# DAC_adapter_V2.net
KiCad netlist of a schematic drawn in EAGLE
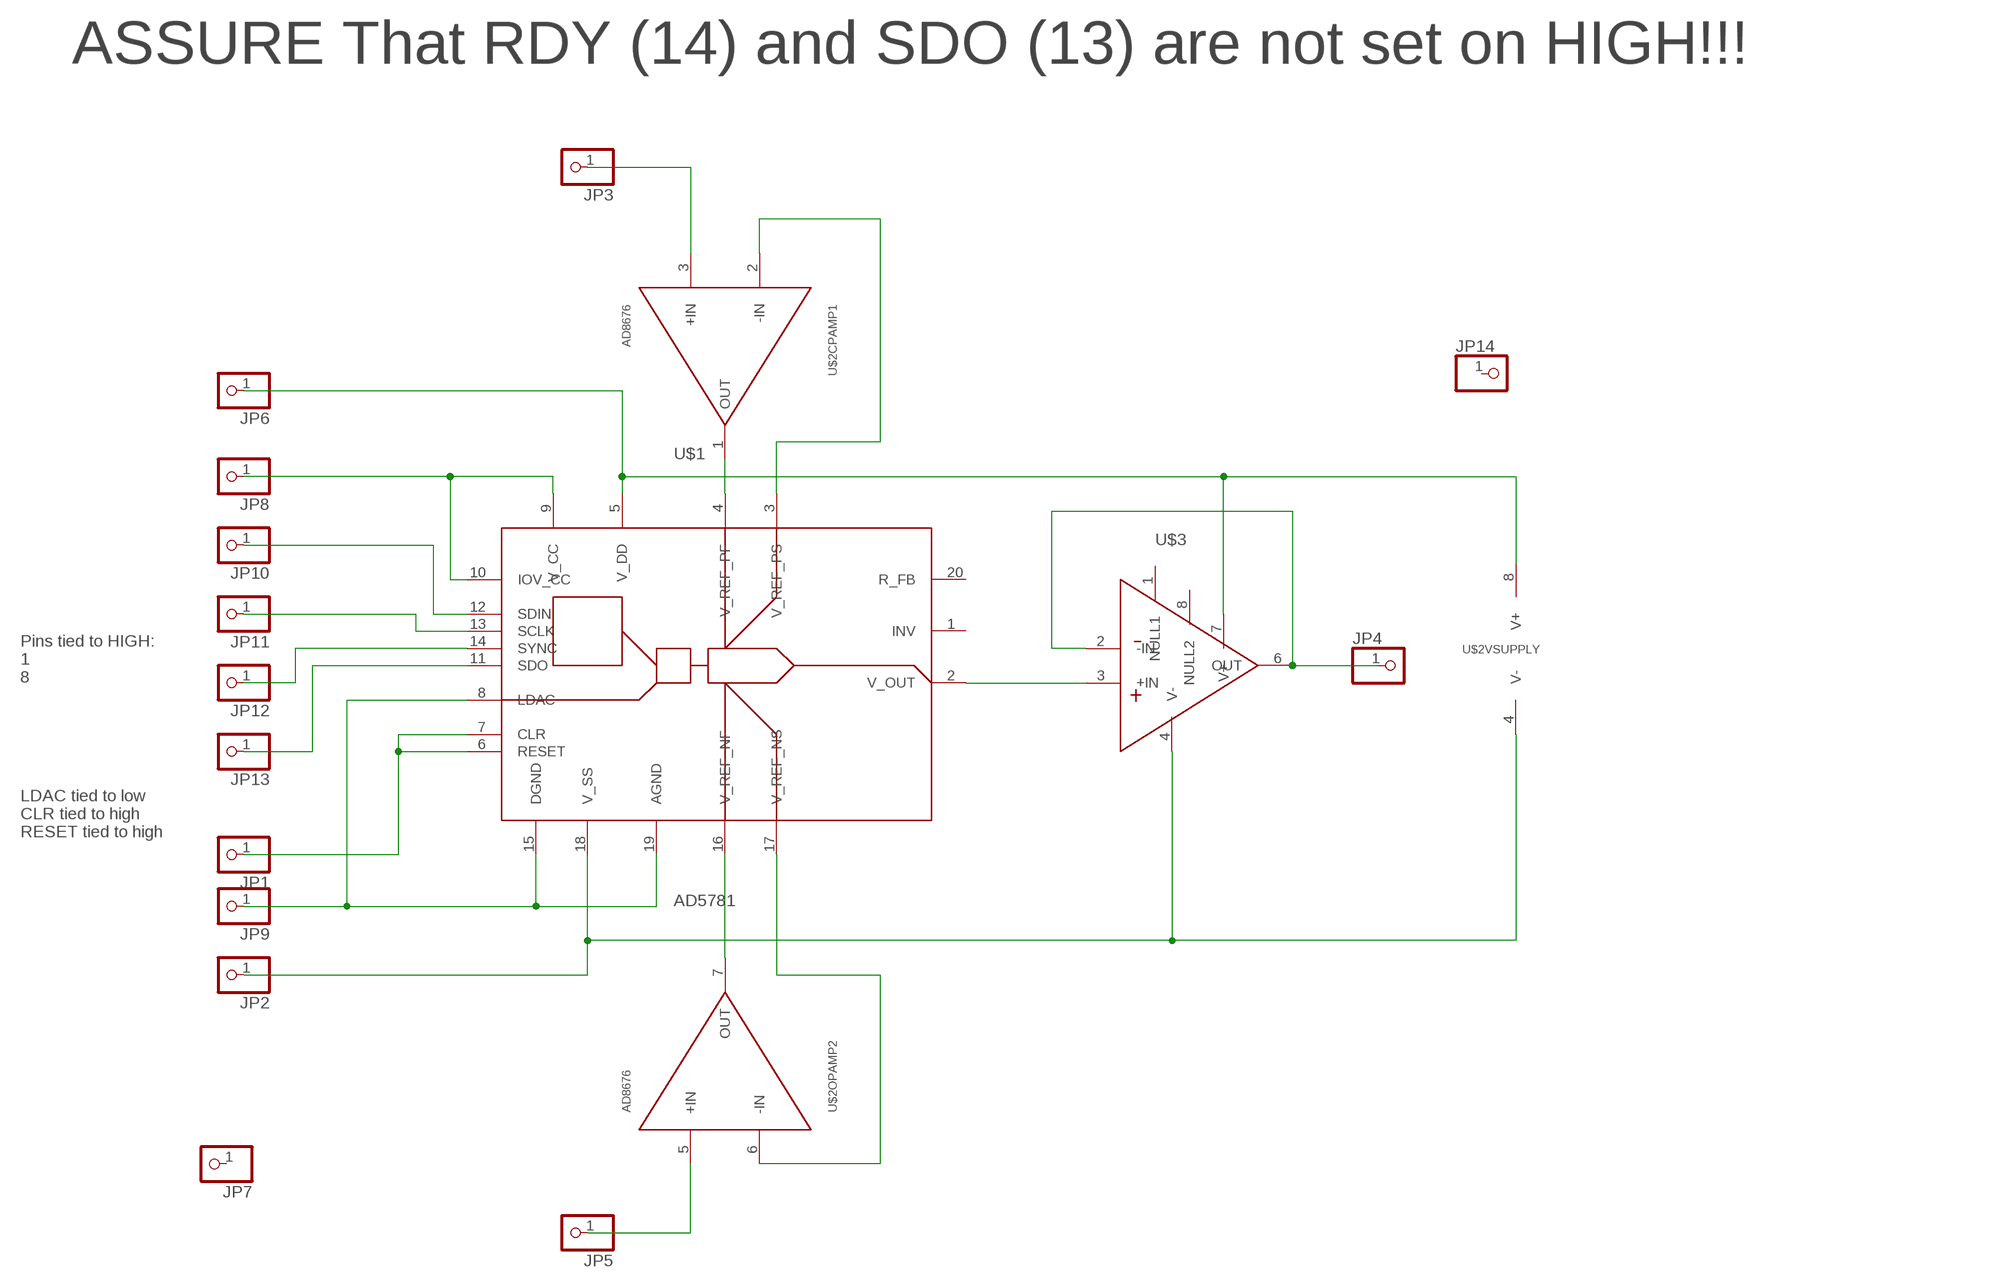
[diagram p0: schematic, sheet 1]

(export (version "E")
  (design (tool "Eeschema 10.0.6"))
  (components
    (comp (ref "JP1")
      (value "PINHD-1X1")
      (footprint "eagle-import:1X01")
      (libsource (lib "eagle-import") (part "PINHD-1X1"))
    )
    (comp (ref "JP2")
      (value "PINHD-1X1")
      (footprint "eagle-import:1X01")
      (libsource (lib "eagle-import") (part "PINHD-1X1"))
    )
    (comp (ref "JP3")
      (value "PINHD-1X1")
      (footprint "eagle-import:1X01")
      (libsource (lib "eagle-import") (part "PINHD-1X1"))
    )
    (comp (ref "JP4")
      (value "PINHD-1X1")
      (footprint "eagle-import:1X01")
      (libsource (lib "eagle-import") (part "PINHD-1X1"))
    )
    (comp (ref "JP5")
      (value "PINHD-1X1")
      (footprint "eagle-import:1X01")
      (libsource (lib "eagle-import") (part "PINHD-1X1"))
    )
    (comp (ref "JP6")
      (value "PINHD-1X1")
      (footprint "eagle-import:1X01")
      (libsource (lib "eagle-import") (part "PINHD-1X1"))
    )
    (comp (ref "JP7")
      (value "PINHD-1X1")
      (footprint "eagle-import:1X01")
      (libsource (lib "eagle-import") (part "PINHD-1X1"))
    )
    (comp (ref "JP8")
      (value "PINHD-1X1")
      (footprint "eagle-import:1X01")
      (libsource (lib "eagle-import") (part "PINHD-1X1"))
    )
    (comp (ref "JP9")
      (value "PINHD-1X1")
      (footprint "eagle-import:1X01")
      (libsource (lib "eagle-import") (part "PINHD-1X1"))
    )
    (comp (ref "JP10")
      (value "PINHD-1X1")
      (footprint "eagle-import:1X01")
      (libsource (lib "eagle-import") (part "PINHD-1X1"))
    )
    (comp (ref "JP11")
      (value "PINHD-1X1")
      (footprint "eagle-import:1X01")
      (libsource (lib "eagle-import") (part "PINHD-1X1"))
    )
    (comp (ref "JP12")
      (value "PINHD-1X1")
      (footprint "eagle-import:1X01")
      (libsource (lib "eagle-import") (part "PINHD-1X1"))
    )
    (comp (ref "JP13")
      (value "PINHD-1X1")
      (footprint "eagle-import:1X01")
      (libsource (lib "eagle-import") (part "PINHD-1X1"))
    )
    (comp (ref "JP14")
      (value "PINHD-1X1")
      (footprint "eagle-import:1X01")
      (libsource (lib "eagle-import") (part "PINHD-1X1"))
    )
    (comp (ref "U$1")
      (value "AD5781")
      (footprint "eagle-import:TSSOP20")
      (libsource (lib "eagle-import") (part "AD5781"))
    )
    (comp (ref "U$2")
      (value "AD8676")
      (footprint "eagle-import:MSOP08")
      (libsource (lib "eagle-import") (part "AD8676"))
    )
    (comp (ref "U$3")
      (value "AD8675")
      (footprint "eagle-import:MSOP08")
      (libsource (lib "eagle-import") (part "AD8675"))
    )
  )
  (nets
    (net (code "1") (name "Net-(U$1-AGND)") (class "Default")
      (node (ref "JP9") (pin "1") (pinfunction "1_1") (pintype "passive"))
      (node (ref "U$1") (pin "15") (pinfunction "DGND_15") (pintype "bidirectional"))
      (node (ref "U$1") (pin "19") (pinfunction "AGND_19") (pintype "bidirectional"))
      (node (ref "U$1") (pin "8") (pinfunction "LDAC_8") (pintype "bidirectional"))
    )
    (net (code "2") (name "Net-(U$1-CLR)") (class "Default")
      (node (ref "JP1") (pin "1") (pinfunction "1_1") (pintype "passive"))
      (node (ref "U$1") (pin "6") (pinfunction "RESET_6") (pintype "bidirectional"))
      (node (ref "U$1") (pin "7") (pinfunction "CLR_7") (pintype "bidirectional"))
    )
    (net (code "3") (name "Net-(U$1-IOV_CC)") (class "Default")
      (node (ref "JP8") (pin "1") (pinfunction "1_1") (pintype "passive"))
      (node (ref "U$1") (pin "10") (pinfunction "IOV_CC_10") (pintype "bidirectional"))
      (node (ref "U$1") (pin "9") (pinfunction "V_CC_9") (pintype "bidirectional"))
    )
    (net (code "4") (name "Net-(U$1-SCLK)") (class "Default")
      (node (ref "JP11") (pin "1") (pinfunction "1_1") (pintype "passive"))
      (node (ref "U$1") (pin "13") (pinfunction "SCLK_13") (pintype "bidirectional"))
    )
    (net (code "5") (name "Net-(U$1-SDIN)") (class "Default")
      (node (ref "JP10") (pin "1") (pinfunction "1_1") (pintype "passive"))
      (node (ref "U$1") (pin "12") (pinfunction "SDIN_12") (pintype "bidirectional"))
    )
    (net (code "6") (name "Net-(U$1-SDO)") (class "Default")
      (node (ref "JP13") (pin "1") (pinfunction "1_1") (pintype "passive"))
      (node (ref "U$1") (pin "11") (pinfunction "SDO_11") (pintype "bidirectional"))
    )
    (net (code "7") (name "Net-(U$1-SYNC)") (class "Default")
      (node (ref "JP12") (pin "1") (pinfunction "1_1") (pintype "passive"))
      (node (ref "U$1") (pin "14") (pinfunction "SYNC_14") (pintype "bidirectional"))
    )
    (net (code "8") (name "Net-(U$1-V_DD)") (class "Default")
      (node (ref "JP6") (pin "1") (pinfunction "1_1") (pintype "passive"))
      (node (ref "U$1") (pin "5") (pinfunction "V_DD_5") (pintype "bidirectional"))
      (node (ref "U$2") (pin "8") (pinfunction "V+_8") (pintype "power_in"))
      (node (ref "U$3") (pin "7") (pinfunction "V+_7") (pintype "bidirectional"))
    )
    (net (code "9") (name "Net-(U$1-V_OUT)") (class "Default")
      (node (ref "U$1") (pin "2") (pinfunction "V_OUT_2") (pintype "bidirectional"))
      (node (ref "U$3") (pin "3") (pinfunction "+IN_3") (pintype "bidirectional"))
    )
    (net (code "10") (name "Net-(U$1-V_REF_NF)") (class "Default")
      (node (ref "U$1") (pin "16") (pinfunction "V_REF_NF_16") (pintype "bidirectional"))
      (node (ref "U$2") (pin "7") (pinfunction "OUT_7") (pintype "bidirectional"))
    )
    (net (code "11") (name "Net-(U$1-V_REF_NS)") (class "Default")
      (node (ref "U$1") (pin "17") (pinfunction "V_REF_NS_17") (pintype "bidirectional"))
      (node (ref "U$2") (pin "6") (pinfunction "-IN_6") (pintype "bidirectional"))
    )
    (net (code "12") (name "Net-(U$1-V_REF_PF)") (class "Default")
      (node (ref "U$1") (pin "4") (pinfunction "V_REF_PF_4") (pintype "bidirectional"))
      (node (ref "U$2") (pin "1") (pinfunction "OUT_1") (pintype "bidirectional"))
    )
    (net (code "13") (name "Net-(U$1-V_REF_PS)") (class "Default")
      (node (ref "U$1") (pin "3") (pinfunction "V_REF_PS_3") (pintype "bidirectional"))
      (node (ref "U$2") (pin "2") (pinfunction "-IN_2") (pintype "bidirectional"))
    )
    (net (code "14") (name "Net-(U$1-V_SS)") (class "Default")
      (node (ref "JP2") (pin "1") (pinfunction "1_1") (pintype "passive"))
      (node (ref "U$1") (pin "18") (pinfunction "V_SS_18") (pintype "bidirectional"))
      (node (ref "U$2") (pin "4") (pinfunction "V-_4") (pintype "power_in"))
      (node (ref "U$3") (pin "4") (pinfunction "V-_4") (pintype "bidirectional"))
    )
    (net (code "15") (name "Net-(U$2A-+IN)") (class "Default")
      (node (ref "JP3") (pin "1") (pinfunction "1_1") (pintype "passive"))
      (node (ref "U$2") (pin "3") (pinfunction "+IN_3") (pintype "bidirectional"))
    )
    (net (code "16") (name "Net-(U$2B-+IN)") (class "Default")
      (node (ref "JP5") (pin "1") (pinfunction "1_1") (pintype "passive"))
      (node (ref "U$2") (pin "5") (pinfunction "+IN_5") (pintype "bidirectional"))
    )
    (net (code "17") (name "Net-(U$3--IN)") (class "Default")
      (node (ref "JP4") (pin "1") (pinfunction "1_1") (pintype "passive"))
      (node (ref "U$3") (pin "2") (pinfunction "-IN_2") (pintype "bidirectional"))
      (node (ref "U$3") (pin "6") (pinfunction "OUT_6") (pintype "bidirectional"))
    )
    (net (code "18") (name "unconnected-(JP7-Pad1)") (class "Default")
      (node (ref "JP7") (pin "1") (pinfunction "1_1") (pintype "passive"))
    )
    (net (code "19") (name "unconnected-(JP14-Pad1)") (class "Default")
      (node (ref "JP14") (pin "1") (pinfunction "1_1") (pintype "passive"))
    )
    (net (code "20") (name "unconnected-(U$1-INV-Pad1)") (class "Default")
      (node (ref "U$1") (pin "1") (pinfunction "INV_1") (pintype "bidirectional"))
    )
    (net (code "21") (name "unconnected-(U$1-R_FB-Pad20)") (class "Default")
      (node (ref "U$1") (pin "20") (pinfunction "R_FB_20") (pintype "bidirectional"))
    )
    (net (code "22") (name "unconnected-(U$3-NULL1-Pad1)") (class "Default")
      (node (ref "U$3") (pin "1") (pinfunction "NULL1_1") (pintype "bidirectional"))
    )
    (net (code "23") (name "unconnected-(U$3-NULL2-Pad8)") (class "Default")
      (node (ref "U$3") (pin "8") (pinfunction "NULL2_8") (pintype "bidirectional"))
    )
  )
)
